# nesa-3_0-unitygain.net
KiCad netlist of a schematic drawn in EAGLE
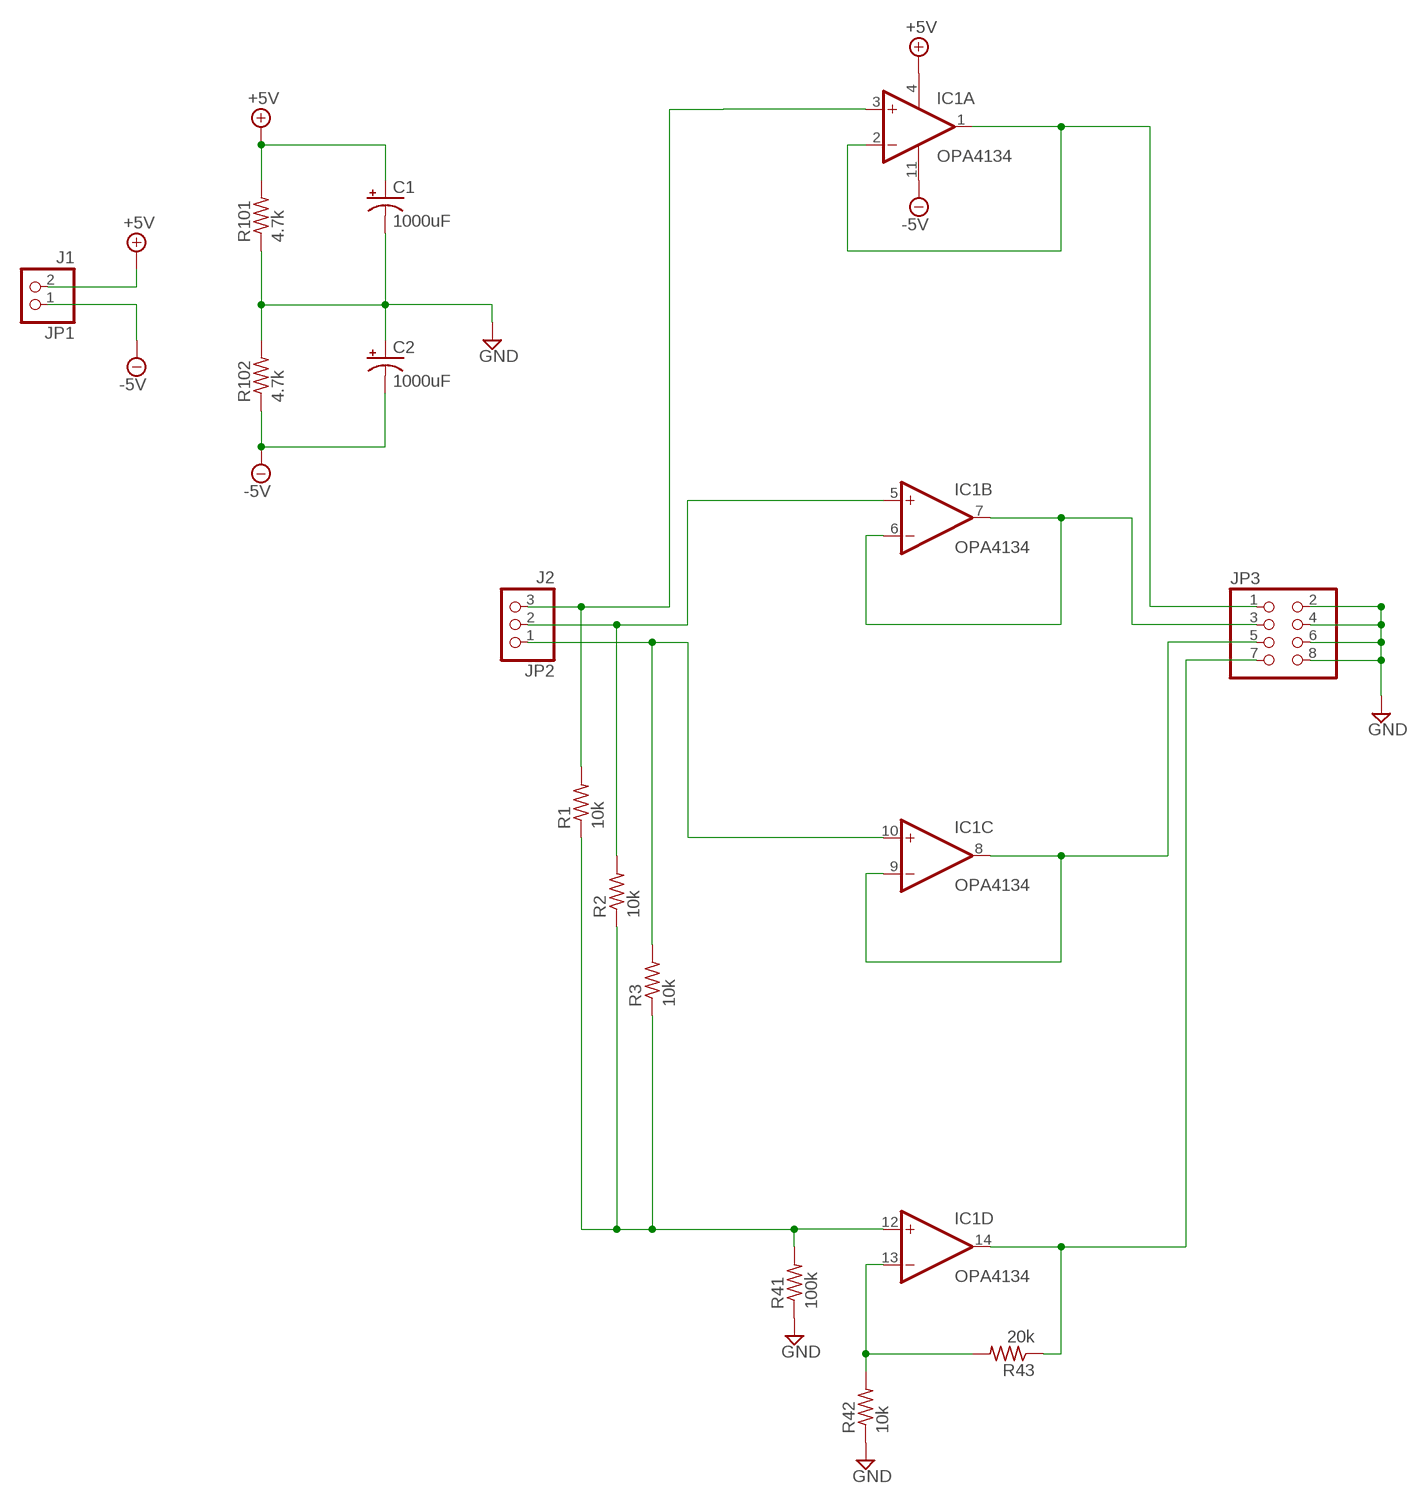
[diagram p0: schematic, sheet 1]

(export (version "E")
  (design (tool "Eeschema 10.0.6"))
  (components
    (comp (ref "C1")
      (value "1000uF")
      (footprint "eagle-import:E3,5-10")
      (libsource (lib "eagle-import") (part "CPOL-USE3.5-10"))
    )
    (comp (ref "C2")
      (value "1000uF")
      (footprint "eagle-import:E3,5-10")
      (libsource (lib "eagle-import") (part "CPOL-USE3.5-10"))
    )
    (comp (ref "IC1")
      (value "OPA4134")
      (footprint "eagle-import:DIL14")
      (libsource (lib "eagle-import") (part "MCP604P"))
    )
    (comp (ref "JP1")
      (value "J1")
      (footprint "eagle-import:1X02")
      (libsource (lib "eagle-import") (part "PINHD-1X2"))
    )
    (comp (ref "JP2")
      (value "J2")
      (footprint "eagle-import:1X03")
      (libsource (lib "eagle-import") (part "PINHD-1X3"))
    )
    (comp (ref "JP3")
      (value "PINHD-2X4")
      (footprint "eagle-import:2X04")
      (libsource (lib "eagle-import") (part "PINHD-2X4"))
    )
    (comp (ref "R1")
      (value "10k")
      (footprint "eagle-import:0204_7")
      (libsource (lib "eagle-import") (part "R-US_0204/7"))
    )
    (comp (ref "R2")
      (value "10k")
      (footprint "eagle-import:0204_7")
      (libsource (lib "eagle-import") (part "R-US_0204/7"))
    )
    (comp (ref "R3")
      (value "10k")
      (footprint "eagle-import:0204_7")
      (libsource (lib "eagle-import") (part "R-US_0204/7"))
    )
    (comp (ref "R41")
      (value "100k")
      (footprint "eagle-import:0204_7")
      (libsource (lib "eagle-import") (part "R-US_0204/7"))
    )
    (comp (ref "R42")
      (value "10k")
      (footprint "eagle-import:0204_7")
      (libsource (lib "eagle-import") (part "R-US_0204/7"))
    )
    (comp (ref "R43")
      (value "20k")
      (footprint "eagle-import:0204_7")
      (libsource (lib "eagle-import") (part "R-US_0204/7"))
    )
    (comp (ref "R101")
      (value "4.7k")
      (footprint "eagle-import:0204_7")
      (libsource (lib "eagle-import") (part "R-US_0204/7"))
    )
    (comp (ref "R102")
      (value "4.7k")
      (footprint "eagle-import:0204_7")
      (libsource (lib "eagle-import") (part "R-US_0204/7"))
    )
  )
  (nets
    (net (code "1") (name "+5V") (class "Default")
      (node (ref "C1") (pin "+") (pinfunction "+_+") (pintype "passive"))
      (node (ref "IC1") (pin "4") (pinfunction "V+_4") (pintype "power_in"))
      (node (ref "JP1") (pin "2") (pinfunction "2_2") (pintype "passive"))
      (node (ref "R101") (pin "2") (pinfunction "2_2") (pintype "passive"))
    )
    (net (code "2") (name "-5V") (class "Default")
      (node (ref "C2") (pin "-") (pinfunction "-_-") (pintype "passive"))
      (node (ref "IC1") (pin "11") (pinfunction "V-_11") (pintype "power_in"))
      (node (ref "JP1") (pin "1") (pinfunction "1_1") (pintype "passive"))
      (node (ref "R102") (pin "1") (pinfunction "1_1") (pintype "passive"))
    )
    (net (code "3") (name "GND") (class "Default")
      (node (ref "C1") (pin "-") (pinfunction "-_-") (pintype "passive"))
      (node (ref "C2") (pin "+") (pinfunction "+_+") (pintype "passive"))
      (node (ref "JP3") (pin "2") (pinfunction "2_2") (pintype "passive"))
      (node (ref "JP3") (pin "4") (pinfunction "4_4") (pintype "passive"))
      (node (ref "JP3") (pin "6") (pinfunction "6_6") (pintype "passive"))
      (node (ref "JP3") (pin "8") (pinfunction "8_8") (pintype "passive"))
      (node (ref "R101") (pin "1") (pinfunction "1_1") (pintype "passive"))
      (node (ref "R102") (pin "2") (pinfunction "2_2") (pintype "passive"))
      (node (ref "R41") (pin "1") (pinfunction "1_1") (pintype "passive"))
      (node (ref "R42") (pin "1") (pinfunction "1_1") (pintype "passive"))
    )
    (net (code "4") (name "Net-(IC1A-+IN)") (class "Default")
      (node (ref "IC1") (pin "3") (pinfunction "+IN_3") (pintype "input"))
      (node (ref "JP2") (pin "3") (pinfunction "3_3") (pintype "passive"))
      (node (ref "R1") (pin "2") (pinfunction "2_2") (pintype "passive"))
    )
    (net (code "5") (name "Net-(IC1A--IN)") (class "Default")
      (node (ref "IC1") (pin "1") (pinfunction "OUT_1") (pintype "output"))
      (node (ref "IC1") (pin "2") (pinfunction "-IN_2") (pintype "input"))
      (node (ref "JP3") (pin "1") (pinfunction "1_1") (pintype "passive"))
    )
    (net (code "6") (name "Net-(IC1B-+IN)") (class "Default")
      (node (ref "IC1") (pin "5") (pinfunction "+IN_5") (pintype "input"))
      (node (ref "JP2") (pin "2") (pinfunction "2_2") (pintype "passive"))
      (node (ref "R2") (pin "2") (pinfunction "2_2") (pintype "passive"))
    )
    (net (code "7") (name "Net-(IC1B--IN)") (class "Default")
      (node (ref "IC1") (pin "6") (pinfunction "-IN_6") (pintype "input"))
      (node (ref "IC1") (pin "7") (pinfunction "OUT_7") (pintype "output"))
      (node (ref "JP3") (pin "3") (pinfunction "3_3") (pintype "passive"))
    )
    (net (code "8") (name "Net-(IC1C-+IN)") (class "Default")
      (node (ref "IC1") (pin "10") (pinfunction "+IN_10") (pintype "input"))
      (node (ref "JP2") (pin "1") (pinfunction "1_1") (pintype "passive"))
      (node (ref "R3") (pin "2") (pinfunction "2_2") (pintype "passive"))
    )
    (net (code "9") (name "Net-(IC1C--IN)") (class "Default")
      (node (ref "IC1") (pin "8") (pinfunction "OUT_8") (pintype "output"))
      (node (ref "IC1") (pin "9") (pinfunction "-IN_9") (pintype "input"))
      (node (ref "JP3") (pin "5") (pinfunction "5_5") (pintype "passive"))
    )
    (net (code "10") (name "Net-(IC1D-+IN)") (class "Default")
      (node (ref "IC1") (pin "12") (pinfunction "+IN_12") (pintype "input"))
      (node (ref "R1") (pin "1") (pinfunction "1_1") (pintype "passive"))
      (node (ref "R2") (pin "1") (pinfunction "1_1") (pintype "passive"))
      (node (ref "R3") (pin "1") (pinfunction "1_1") (pintype "passive"))
      (node (ref "R41") (pin "2") (pinfunction "2_2") (pintype "passive"))
    )
    (net (code "11") (name "Net-(IC1D--IN)") (class "Default")
      (node (ref "IC1") (pin "13") (pinfunction "-IN_13") (pintype "input"))
      (node (ref "R42") (pin "2") (pinfunction "2_2") (pintype "passive"))
      (node (ref "R43") (pin "2") (pinfunction "2_2") (pintype "passive"))
    )
    (net (code "12") (name "Net-(IC1D-OUT)") (class "Default")
      (node (ref "IC1") (pin "14") (pinfunction "OUT_14") (pintype "output"))
      (node (ref "JP3") (pin "7") (pinfunction "7_7") (pintype "passive"))
      (node (ref "R43") (pin "1") (pinfunction "1_1") (pintype "passive"))
    )
  )
)
